# STRWHL-S04-V00-PSU.net
KiCad netlist of a schematic drawn in Altium Designer
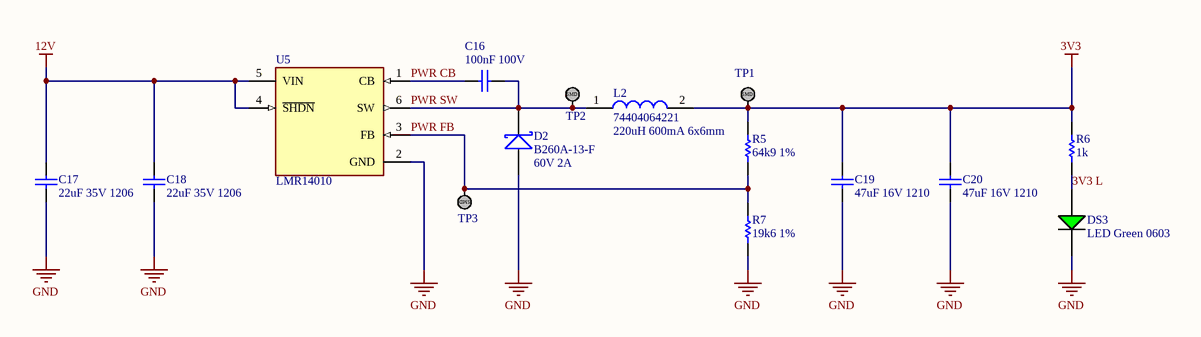
[diagram p0: STRWHL-S04-V00-PSU.SchDoc]

(export (version "E")
  (design (tool "Eeschema 10.0.6"))
  (components
    (comp (ref "C16")
      (value "100nF 100V")
      (footprint "Cap_Ceramic_0603")
      (description "Capacitor, Ceramic, SMD, 100nF, 100V, 5%, X7R, 0603")
      (libsource (lib "StandardCapacitors") (part "100nF 100V 5% X7R 0603"))
    )
    (comp (ref "C17")
      (value "22uF 35V 1206")
      (footprint "Cap_Ceramic_1206")
      (description "Capacitor, Ceramic, SMD, 22uF, 35V, 10%, X7R, 1206")
      (libsource (lib "StandardCapacitors") (part "22uF 35V 10% X7R 1206"))
    )
    (comp (ref "C18")
      (value "22uF 35V 1206")
      (footprint "Cap_Ceramic_1206")
      (description "Capacitor, Ceramic, SMD, 22uF, 35V, 10%, X7R, 1206")
      (libsource (lib "StandardCapacitors") (part "22uF 35V 10% X7R 1206"))
    )
    (comp (ref "C19")
      (value "47uF 16V 1210")
      (footprint "Cap_Ceramic_1210")
      (description "Capacitor, Ceramic, SMD, 47uF, 16V, 5%, X7R, 1210")
      (libsource (lib "StandardCapacitors") (part "47uF 16V 10% X7R 1210"))
    )
    (comp (ref "C20")
      (value "47uF 16V 1210")
      (footprint "Cap_Ceramic_1210")
      (description "Capacitor, Ceramic, SMD, 47uF, 16V, 5%, X7R, 1210")
      (libsource (lib "StandardCapacitors") (part "47uF 16V 10% X7R 1210"))
    )
    (comp (ref "D2")
      (value "B260A-13-F")
      (footprint "SMA")
      (description "Diode, Schottky Barrier Rectifier, 60 V, 2 A, B260A-13-F")
      (libsource (lib "QUTMS_DiodeLibrary") (part "B260A-13-F"))
    )
    (comp (ref "DS3")
      (value "LED Green 0603")
      (footprint "LED GREEN 0603")
      (libsource (lib "QUTMS_LEDLibrary") (part "LED Green 0603"))
    )
    (comp (ref "L2")
      (value "74404064221")
      (footprint "Inductor_6x6mm")
      (description "FIXED IND 220UH 660MA 850 MOHM")
      (libsource (lib "QUTMS_InductorLibrary") (part "74404064221"))
    )
    (comp (ref "R5")
      (value "64k9 1%")
      (footprint "Res_ThinFilm_0603")
      (description "Resistor, SMD, 64k9, 0.1W, 5%, 0603")
      (libsource (lib "StandardResistors") (part "64k9 1% 0603"))
    )
    (comp (ref "R6")
      (value "1k")
      (footprint "Res_ThinFilm_0603")
      (description "Resistor, SMD, 1k, 0.1W, 5%, 0603")
      (libsource (lib "StandardResistors") (part "1k 5% 0603"))
    )
    (comp (ref "R7")
      (value "19k6 1%")
      (footprint "Res_ThinFilm_0603")
      (description "Resistor, SMD, 19k6, 0.1W, 5%, 0603")
      (libsource (lib "StandardResistors") (part "19k6 1% 0603"))
    )
    (comp (ref "TP1")
      (value "TestPoint_SMD")
      (footprint "TestPointSMD")
      (libsource (lib "StandardTest") (part "TestPoint_SMD"))
    )
    (comp (ref "TP2")
      (value "TestPoint_SMD")
      (footprint "TestPointSMD")
      (libsource (lib "StandardTest") (part "TestPoint_SMD"))
    )
    (comp (ref "TP3")
      (value "TestPoint_SMD")
      (footprint "TestPointSMD")
      (libsource (lib "StandardTest") (part "TestPoint_SMD"))
    )
    (comp (ref "U5")
      (value "LMR14010")
      (footprint "LMR14010")
      (libsource (lib "QUTMS_PowerSupplyLibrary") (part "LMR14010"))
    )
  )
  (nets
    (net (code "1") (name "/3V3 L") (class "Default")
      (node (ref "DS3") (pin "1") (pinfunction "A_1") (pintype "passive"))
      (node (ref "R6") (pin "1") (pinfunction "1_1") (pintype "passive"))
    )
    (net (code "2") (name "/PWR CB") (class "Default")
      (node (ref "C16") (pin "1") (pinfunction "1_1") (pintype "passive"))
      (node (ref "U5") (pin "1") (pinfunction "CB_1") (pintype "input"))
    )
    (net (code "3") (name "/PWR FB") (class "Default")
      (node (ref "R5") (pin "1") (pinfunction "1_1") (pintype "passive"))
      (node (ref "R7") (pin "2") (pinfunction "2_2") (pintype "passive"))
      (node (ref "TP3") (pin "1") (pinfunction "1_1") (pintype "passive"))
      (node (ref "U5") (pin "3") (pinfunction "FB_3") (pintype "input"))
    )
    (net (code "4") (name "/PWR SW") (class "Default")
      (node (ref "C16") (pin "2") (pinfunction "2_2") (pintype "passive"))
      (node (ref "D2") (pin "K") (pinfunction "K_K") (pintype "passive"))
      (node (ref "L2") (pin "1") (pinfunction "1_1") (pintype "passive"))
      (node (ref "TP2") (pin "1") (pinfunction "1_1") (pintype "passive"))
      (node (ref "U5") (pin "6") (pinfunction "SW_6") (pintype "output"))
    )
    (net (code "5") (name "3V3") (class "Default")
      (node (ref "C19") (pin "2") (pinfunction "2_2") (pintype "passive"))
      (node (ref "C20") (pin "2") (pinfunction "2_2") (pintype "passive"))
      (node (ref "L2") (pin "2") (pinfunction "2_2") (pintype "passive"))
      (node (ref "R5") (pin "2") (pinfunction "2_2") (pintype "passive"))
      (node (ref "R6") (pin "2") (pinfunction "2_2") (pintype "passive"))
      (node (ref "TP1") (pin "1") (pinfunction "1_1") (pintype "passive"))
    )
    (net (code "6") (name "12V") (class "Default")
      (node (ref "C17") (pin "2") (pinfunction "2_2") (pintype "passive"))
      (node (ref "C18") (pin "2") (pinfunction "2_2") (pintype "passive"))
      (node (ref "U5") (pin "4") (pinfunction "~{SHDN}_4") (pintype "input"))
      (node (ref "U5") (pin "5") (pinfunction "VIN_5") (pintype "power_in"))
    )
    (net (code "7") (name "GND") (class "Default")
      (node (ref "C17") (pin "1") (pinfunction "1_1") (pintype "passive"))
      (node (ref "C18") (pin "1") (pinfunction "1_1") (pintype "passive"))
      (node (ref "C19") (pin "1") (pinfunction "1_1") (pintype "passive"))
      (node (ref "C20") (pin "1") (pinfunction "1_1") (pintype "passive"))
      (node (ref "D2") (pin "A") (pinfunction "A_A") (pintype "passive"))
      (node (ref "DS3") (pin "2") (pinfunction "C_2") (pintype "passive"))
      (node (ref "R7") (pin "1") (pinfunction "1_1") (pintype "passive"))
      (node (ref "U5") (pin "2") (pinfunction "GND_2") (pintype "power_in"))
    )
  )
)
